# 8bitPig-PigstyGates_v2-frontPCB.net
KiCad netlist of a schematic drawn in EAGLE
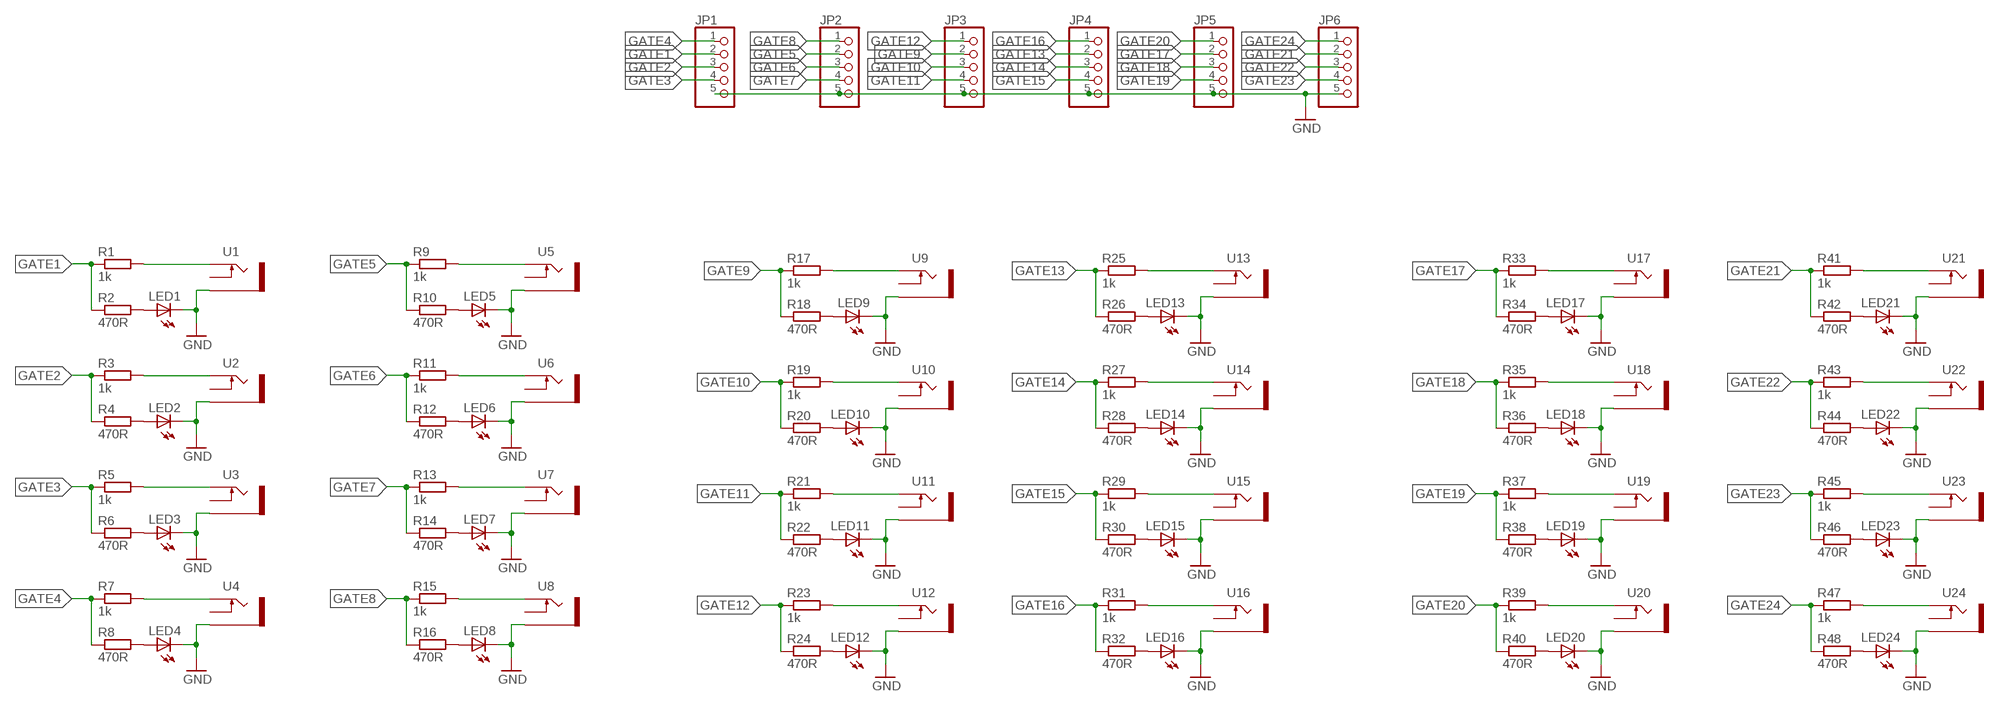
[diagram p0: schematic, sheet 1]

(export (version "E")
  (design (tool "Eeschema 10.0.6"))
  (components
    (comp (ref "JP1")
      (value "PINHD-1X5")
      (footprint "eagle-import:1X05")
      (libsource (lib "eagle-import") (part "PINHD-1X5"))
    )
    (comp (ref "JP2")
      (value "PINHD-1X5")
      (footprint "eagle-import:1X05")
      (libsource (lib "eagle-import") (part "PINHD-1X5"))
    )
    (comp (ref "JP3")
      (value "PINHD-1X5")
      (footprint "eagle-import:1X05")
      (libsource (lib "eagle-import") (part "PINHD-1X5"))
    )
    (comp (ref "JP4")
      (value "PINHD-1X5")
      (footprint "eagle-import:1X05")
      (libsource (lib "eagle-import") (part "PINHD-1X5"))
    )
    (comp (ref "JP5")
      (value "PINHD-1X5")
      (footprint "eagle-import:1X05")
      (libsource (lib "eagle-import") (part "PINHD-1X5"))
    )
    (comp (ref "JP6")
      (value "PINHD-1X5")
      (footprint "eagle-import:1X05")
      (libsource (lib "eagle-import") (part "PINHD-1X5"))
    )
    (comp (ref "LED1")
      (value "LED3MM")
      (footprint "eagle-import:LED3MM")
      (libsource (lib "eagle-import") (part "LED3MM"))
    )
    (comp (ref "LED2")
      (value "LED3MM")
      (footprint "eagle-import:LED3MM")
      (libsource (lib "eagle-import") (part "LED3MM"))
    )
    (comp (ref "LED3")
      (value "LED3MM")
      (footprint "eagle-import:LED3MM")
      (libsource (lib "eagle-import") (part "LED3MM"))
    )
    (comp (ref "LED4")
      (value "LED3MM")
      (footprint "eagle-import:LED3MM")
      (libsource (lib "eagle-import") (part "LED3MM"))
    )
    (comp (ref "LED5")
      (value "LED3MM")
      (footprint "eagle-import:LED3MM")
      (libsource (lib "eagle-import") (part "LED3MM"))
    )
    (comp (ref "LED6")
      (value "LED3MM")
      (footprint "eagle-import:LED3MM")
      (libsource (lib "eagle-import") (part "LED3MM"))
    )
    (comp (ref "LED7")
      (value "LED3MM")
      (footprint "eagle-import:LED3MM")
      (libsource (lib "eagle-import") (part "LED3MM"))
    )
    (comp (ref "LED8")
      (value "LED3MM")
      (footprint "eagle-import:LED3MM")
      (libsource (lib "eagle-import") (part "LED3MM"))
    )
    (comp (ref "LED9")
      (value "LED3MM")
      (footprint "eagle-import:LED3MM")
      (libsource (lib "eagle-import") (part "LED3MM"))
    )
    (comp (ref "LED10")
      (value "LED3MM")
      (footprint "eagle-import:LED3MM")
      (libsource (lib "eagle-import") (part "LED3MM"))
    )
    (comp (ref "LED11")
      (value "LED3MM")
      (footprint "eagle-import:LED3MM")
      (libsource (lib "eagle-import") (part "LED3MM"))
    )
    (comp (ref "LED12")
      (value "LED3MM")
      (footprint "eagle-import:LED3MM")
      (libsource (lib "eagle-import") (part "LED3MM"))
    )
    (comp (ref "LED13")
      (value "LED3MM")
      (footprint "eagle-import:LED3MM")
      (libsource (lib "eagle-import") (part "LED3MM"))
    )
    (comp (ref "LED14")
      (value "LED3MM")
      (footprint "eagle-import:LED3MM")
      (libsource (lib "eagle-import") (part "LED3MM"))
    )
    (comp (ref "LED15")
      (value "LED3MM")
      (footprint "eagle-import:LED3MM")
      (libsource (lib "eagle-import") (part "LED3MM"))
    )
    (comp (ref "LED16")
      (value "LED3MM")
      (footprint "eagle-import:LED3MM")
      (libsource (lib "eagle-import") (part "LED3MM"))
    )
    (comp (ref "LED17")
      (value "LED3MM")
      (footprint "eagle-import:LED3MM")
      (libsource (lib "eagle-import") (part "LED3MM"))
    )
    (comp (ref "LED18")
      (value "LED3MM")
      (footprint "eagle-import:LED3MM")
      (libsource (lib "eagle-import") (part "LED3MM"))
    )
    (comp (ref "LED19")
      (value "LED3MM")
      (footprint "eagle-import:LED3MM")
      (libsource (lib "eagle-import") (part "LED3MM"))
    )
    (comp (ref "LED20")
      (value "LED3MM")
      (footprint "eagle-import:LED3MM")
      (libsource (lib "eagle-import") (part "LED3MM"))
    )
    (comp (ref "LED21")
      (value "LED3MM")
      (footprint "eagle-import:LED3MM")
      (libsource (lib "eagle-import") (part "LED3MM"))
    )
    (comp (ref "LED22")
      (value "LED3MM")
      (footprint "eagle-import:LED3MM")
      (libsource (lib "eagle-import") (part "LED3MM"))
    )
    (comp (ref "LED23")
      (value "LED3MM")
      (footprint "eagle-import:LED3MM")
      (libsource (lib "eagle-import") (part "LED3MM"))
    )
    (comp (ref "LED24")
      (value "LED3MM")
      (footprint "eagle-import:LED3MM")
      (libsource (lib "eagle-import") (part "LED3MM"))
    )
    (comp (ref "R1")
      (value "1k")
      (footprint "eagle-import:R0603")
      (libsource (lib "eagle-import") (part "R-EU_R0603"))
    )
    (comp (ref "R2")
      (value "470R")
      (footprint "eagle-import:R0603")
      (libsource (lib "eagle-import") (part "R-EU_R0603"))
    )
    (comp (ref "R3")
      (value "1k")
      (footprint "eagle-import:R0603")
      (libsource (lib "eagle-import") (part "R-EU_R0603"))
    )
    (comp (ref "R4")
      (value "470R")
      (footprint "eagle-import:R0603")
      (libsource (lib "eagle-import") (part "R-EU_R0603"))
    )
    (comp (ref "R5")
      (value "1k")
      (footprint "eagle-import:R0603")
      (libsource (lib "eagle-import") (part "R-EU_R0603"))
    )
    (comp (ref "R6")
      (value "470R")
      (footprint "eagle-import:R0603")
      (libsource (lib "eagle-import") (part "R-EU_R0603"))
    )
    (comp (ref "R7")
      (value "1k")
      (footprint "eagle-import:R0603")
      (libsource (lib "eagle-import") (part "R-EU_R0603"))
    )
    (comp (ref "R8")
      (value "470R")
      (footprint "eagle-import:R0603")
      (libsource (lib "eagle-import") (part "R-EU_R0603"))
    )
    (comp (ref "R9")
      (value "1k")
      (footprint "eagle-import:R0603")
      (libsource (lib "eagle-import") (part "R-EU_R0603"))
    )
    (comp (ref "R10")
      (value "470R")
      (footprint "eagle-import:R0603")
      (libsource (lib "eagle-import") (part "R-EU_R0603"))
    )
    (comp (ref "R11")
      (value "1k")
      (footprint "eagle-import:R0603")
      (libsource (lib "eagle-import") (part "R-EU_R0603"))
    )
    (comp (ref "R12")
      (value "470R")
      (footprint "eagle-import:R0603")
      (libsource (lib "eagle-import") (part "R-EU_R0603"))
    )
    (comp (ref "R13")
      (value "1k")
      (footprint "eagle-import:R0603")
      (libsource (lib "eagle-import") (part "R-EU_R0603"))
    )
    (comp (ref "R14")
      (value "470R")
      (footprint "eagle-import:R0603")
      (libsource (lib "eagle-import") (part "R-EU_R0603"))
    )
    (comp (ref "R15")
      (value "1k")
      (footprint "eagle-import:R0603")
      (libsource (lib "eagle-import") (part "R-EU_R0603"))
    )
    (comp (ref "R16")
      (value "470R")
      (footprint "eagle-import:R0603")
      (libsource (lib "eagle-import") (part "R-EU_R0603"))
    )
    (comp (ref "R17")
      (value "1k")
      (footprint "eagle-import:R0603")
      (libsource (lib "eagle-import") (part "R-EU_R0603"))
    )
    (comp (ref "R18")
      (value "470R")
      (footprint "eagle-import:R0603")
      (libsource (lib "eagle-import") (part "R-EU_R0603"))
    )
    (comp (ref "R19")
      (value "1k")
      (footprint "eagle-import:R0603")
      (libsource (lib "eagle-import") (part "R-EU_R0603"))
    )
    (comp (ref "R20")
      (value "470R")
      (footprint "eagle-import:R0603")
      (libsource (lib "eagle-import") (part "R-EU_R0603"))
    )
    (comp (ref "R21")
      (value "1k")
      (footprint "eagle-import:R0603")
      (libsource (lib "eagle-import") (part "R-EU_R0603"))
    )
    (comp (ref "R22")
      (value "470R")
      (footprint "eagle-import:R0603")
      (libsource (lib "eagle-import") (part "R-EU_R0603"))
    )
    (comp (ref "R23")
      (value "1k")
      (footprint "eagle-import:R0603")
      (libsource (lib "eagle-import") (part "R-EU_R0603"))
    )
    (comp (ref "R24")
      (value "470R")
      (footprint "eagle-import:R0603")
      (libsource (lib "eagle-import") (part "R-EU_R0603"))
    )
    (comp (ref "R25")
      (value "1k")
      (footprint "eagle-import:R0603")
      (libsource (lib "eagle-import") (part "R-EU_R0603"))
    )
    (comp (ref "R26")
      (value "470R")
      (footprint "eagle-import:R0603")
      (libsource (lib "eagle-import") (part "R-EU_R0603"))
    )
    (comp (ref "R27")
      (value "1k")
      (footprint "eagle-import:R0603")
      (libsource (lib "eagle-import") (part "R-EU_R0603"))
    )
    (comp (ref "R28")
      (value "470R")
      (footprint "eagle-import:R0603")
      (libsource (lib "eagle-import") (part "R-EU_R0603"))
    )
    (comp (ref "R29")
      (value "1k")
      (footprint "eagle-import:R0603")
      (libsource (lib "eagle-import") (part "R-EU_R0603"))
    )
    (comp (ref "R30")
      (value "470R")
      (footprint "eagle-import:R0603")
      (libsource (lib "eagle-import") (part "R-EU_R0603"))
    )
    (comp (ref "R31")
      (value "1k")
      (footprint "eagle-import:R0603")
      (libsource (lib "eagle-import") (part "R-EU_R0603"))
    )
    (comp (ref "R32")
      (value "470R")
      (footprint "eagle-import:R0603")
      (libsource (lib "eagle-import") (part "R-EU_R0603"))
    )
    (comp (ref "R33")
      (value "1k")
      (footprint "eagle-import:R0603")
      (libsource (lib "eagle-import") (part "R-EU_R0603"))
    )
    (comp (ref "R34")
      (value "470R")
      (footprint "eagle-import:R0603")
      (libsource (lib "eagle-import") (part "R-EU_R0603"))
    )
    (comp (ref "R35")
      (value "1k")
      (footprint "eagle-import:R0603")
      (libsource (lib "eagle-import") (part "R-EU_R0603"))
    )
    (comp (ref "R36")
      (value "470R")
      (footprint "eagle-import:R0603")
      (libsource (lib "eagle-import") (part "R-EU_R0603"))
    )
    (comp (ref "R37")
      (value "1k")
      (footprint "eagle-import:R0603")
      (libsource (lib "eagle-import") (part "R-EU_R0603"))
    )
    (comp (ref "R38")
      (value "470R")
      (footprint "eagle-import:R0603")
      (libsource (lib "eagle-import") (part "R-EU_R0603"))
    )
    (comp (ref "R39")
      (value "1k")
      (footprint "eagle-import:R0603")
      (libsource (lib "eagle-import") (part "R-EU_R0603"))
    )
    (comp (ref "R40")
      (value "470R")
      (footprint "eagle-import:R0603")
      (libsource (lib "eagle-import") (part "R-EU_R0603"))
    )
    (comp (ref "R41")
      (value "1k")
      (footprint "eagle-import:R0603")
      (libsource (lib "eagle-import") (part "R-EU_R0603"))
    )
    (comp (ref "R42")
      (value "470R")
      (footprint "eagle-import:R0603")
      (libsource (lib "eagle-import") (part "R-EU_R0603"))
    )
    (comp (ref "R43")
      (value "1k")
      (footprint "eagle-import:R0603")
      (libsource (lib "eagle-import") (part "R-EU_R0603"))
    )
    (comp (ref "R44")
      (value "470R")
      (footprint "eagle-import:R0603")
      (libsource (lib "eagle-import") (part "R-EU_R0603"))
    )
    (comp (ref "R45")
      (value "1k")
      (footprint "eagle-import:R0603")
      (libsource (lib "eagle-import") (part "R-EU_R0603"))
    )
    (comp (ref "R46")
      (value "470R")
      (footprint "eagle-import:R0603")
      (libsource (lib "eagle-import") (part "R-EU_R0603"))
    )
    (comp (ref "R47")
      (value "1k")
      (footprint "eagle-import:R0603")
      (libsource (lib "eagle-import") (part "R-EU_R0603"))
    )
    (comp (ref "R48")
      (value "470R")
      (footprint "eagle-import:R0603")
      (libsource (lib "eagle-import") (part "R-EU_R0603"))
    )
    (comp (ref "U1")
      (value "THONKICONNNEW")
      (footprint "eagle-import:WQP-PJ301M-12_JACK")
      (libsource (lib "eagle-import") (part "THONKICONNNEW"))
    )
    (comp (ref "U2")
      (value "THONKICONNNEW")
      (footprint "eagle-import:WQP-PJ301M-12_JACK")
      (libsource (lib "eagle-import") (part "THONKICONNNEW"))
    )
    (comp (ref "U3")
      (value "THONKICONNNEW")
      (footprint "eagle-import:WQP-PJ301M-12_JACK")
      (libsource (lib "eagle-import") (part "THONKICONNNEW"))
    )
    (comp (ref "U4")
      (value "THONKICONNNEW")
      (footprint "eagle-import:WQP-PJ301M-12_JACK")
      (libsource (lib "eagle-import") (part "THONKICONNNEW"))
    )
    (comp (ref "U5")
      (value "THONKICONNNEW")
      (footprint "eagle-import:WQP-PJ301M-12_JACK")
      (libsource (lib "eagle-import") (part "THONKICONNNEW"))
    )
    (comp (ref "U6")
      (value "THONKICONNNEW")
      (footprint "eagle-import:WQP-PJ301M-12_JACK")
      (libsource (lib "eagle-import") (part "THONKICONNNEW"))
    )
    (comp (ref "U7")
      (value "THONKICONNNEW")
      (footprint "eagle-import:WQP-PJ301M-12_JACK")
      (libsource (lib "eagle-import") (part "THONKICONNNEW"))
    )
    (comp (ref "U8")
      (value "THONKICONNNEW")
      (footprint "eagle-import:WQP-PJ301M-12_JACK")
      (libsource (lib "eagle-import") (part "THONKICONNNEW"))
    )
    (comp (ref "U9")
      (value "THONKICONNNEW")
      (footprint "eagle-import:WQP-PJ301M-12_JACK")
      (libsource (lib "eagle-import") (part "THONKICONNNEW"))
    )
    (comp (ref "U10")
      (value "THONKICONNNEW")
      (footprint "eagle-import:WQP-PJ301M-12_JACK")
      (libsource (lib "eagle-import") (part "THONKICONNNEW"))
    )
    (comp (ref "U11")
      (value "THONKICONNNEW")
      (footprint "eagle-import:WQP-PJ301M-12_JACK")
      (libsource (lib "eagle-import") (part "THONKICONNNEW"))
    )
    (comp (ref "U12")
      (value "THONKICONNNEW")
      (footprint "eagle-import:WQP-PJ301M-12_JACK")
      (libsource (lib "eagle-import") (part "THONKICONNNEW"))
    )
    (comp (ref "U13")
      (value "THONKICONNNEW")
      (footprint "eagle-import:WQP-PJ301M-12_JACK")
      (libsource (lib "eagle-import") (part "THONKICONNNEW"))
    )
    (comp (ref "U14")
      (value "THONKICONNNEW")
      (footprint "eagle-import:WQP-PJ301M-12_JACK")
      (libsource (lib "eagle-import") (part "THONKICONNNEW"))
    )
    (comp (ref "U15")
      (value "THONKICONNNEW")
      (footprint "eagle-import:WQP-PJ301M-12_JACK")
      (libsource (lib "eagle-import") (part "THONKICONNNEW"))
    )
    (comp (ref "U16")
      (value "THONKICONNNEW")
      (footprint "eagle-import:WQP-PJ301M-12_JACK")
      (libsource (lib "eagle-import") (part "THONKICONNNEW"))
    )
    (comp (ref "U17")
      (value "THONKICONNNEW")
      (footprint "eagle-import:WQP-PJ301M-12_JACK")
      (libsource (lib "eagle-import") (part "THONKICONNNEW"))
    )
    (comp (ref "U18")
      (value "THONKICONNNEW")
      (footprint "eagle-import:WQP-PJ301M-12_JACK")
      (libsource (lib "eagle-import") (part "THONKICONNNEW"))
    )
    (comp (ref "U19")
      (value "THONKICONNNEW")
      (footprint "eagle-import:WQP-PJ301M-12_JACK")
      (libsource (lib "eagle-import") (part "THONKICONNNEW"))
    )
    (comp (ref "U20")
      (value "THONKICONNNEW")
      (footprint "eagle-import:WQP-PJ301M-12_JACK")
      (libsource (lib "eagle-import") (part "THONKICONNNEW"))
    )
    (comp (ref "U21")
      (value "THONKICONNNEW")
      (footprint "eagle-import:WQP-PJ301M-12_JACK")
      (libsource (lib "eagle-import") (part "THONKICONNNEW"))
    )
    (comp (ref "U22")
      (value "THONKICONNNEW")
      (footprint "eagle-import:WQP-PJ301M-12_JACK")
      (libsource (lib "eagle-import") (part "THONKICONNNEW"))
    )
    (comp (ref "U23")
      (value "THONKICONNNEW")
      (footprint "eagle-import:WQP-PJ301M-12_JACK")
      (libsource (lib "eagle-import") (part "THONKICONNNEW"))
    )
    (comp (ref "U24")
      (value "THONKICONNNEW")
      (footprint "eagle-import:WQP-PJ301M-12_JACK")
      (libsource (lib "eagle-import") (part "THONKICONNNEW"))
    )
  )
  (nets
    (net (code "1") (name "GATE1") (class "Default")
      (node (ref "JP1") (pin "2") (pinfunction "2_2") (pintype "passive"))
      (node (ref "R1") (pin "1") (pinfunction "1_1") (pintype "passive"))
      (node (ref "R2") (pin "1") (pinfunction "1_1") (pintype "passive"))
    )
    (net (code "2") (name "GATE2") (class "Default")
      (node (ref "JP1") (pin "3") (pinfunction "3_3") (pintype "passive"))
      (node (ref "R3") (pin "1") (pinfunction "1_1") (pintype "passive"))
      (node (ref "R4") (pin "1") (pinfunction "1_1") (pintype "passive"))
    )
    (net (code "3") (name "GATE3") (class "Default")
      (node (ref "JP1") (pin "4") (pinfunction "4_4") (pintype "passive"))
      (node (ref "R5") (pin "1") (pinfunction "1_1") (pintype "passive"))
      (node (ref "R6") (pin "1") (pinfunction "1_1") (pintype "passive"))
    )
    (net (code "4") (name "GATE4") (class "Default")
      (node (ref "JP1") (pin "1") (pinfunction "1_1") (pintype "passive"))
      (node (ref "R7") (pin "1") (pinfunction "1_1") (pintype "passive"))
      (node (ref "R8") (pin "1") (pinfunction "1_1") (pintype "passive"))
    )
    (net (code "5") (name "GATE5") (class "Default")
      (node (ref "JP2") (pin "2") (pinfunction "2_2") (pintype "passive"))
      (node (ref "R10") (pin "1") (pinfunction "1_1") (pintype "passive"))
      (node (ref "R9") (pin "1") (pinfunction "1_1") (pintype "passive"))
    )
    (net (code "6") (name "GATE6") (class "Default")
      (node (ref "JP2") (pin "3") (pinfunction "3_3") (pintype "passive"))
      (node (ref "R11") (pin "1") (pinfunction "1_1") (pintype "passive"))
      (node (ref "R12") (pin "1") (pinfunction "1_1") (pintype "passive"))
    )
    (net (code "7") (name "GATE7") (class "Default")
      (node (ref "JP2") (pin "4") (pinfunction "4_4") (pintype "passive"))
      (node (ref "R13") (pin "1") (pinfunction "1_1") (pintype "passive"))
      (node (ref "R14") (pin "1") (pinfunction "1_1") (pintype "passive"))
    )
    (net (code "8") (name "GATE8") (class "Default")
      (node (ref "JP2") (pin "1") (pinfunction "1_1") (pintype "passive"))
      (node (ref "R15") (pin "1") (pinfunction "1_1") (pintype "passive"))
      (node (ref "R16") (pin "1") (pinfunction "1_1") (pintype "passive"))
    )
    (net (code "9") (name "GATE9") (class "Default")
      (node (ref "JP3") (pin "2") (pinfunction "2_2") (pintype "passive"))
      (node (ref "R17") (pin "1") (pinfunction "1_1") (pintype "passive"))
      (node (ref "R18") (pin "1") (pinfunction "1_1") (pintype "passive"))
    )
    (net (code "10") (name "GATE10") (class "Default")
      (node (ref "JP3") (pin "3") (pinfunction "3_3") (pintype "passive"))
      (node (ref "R19") (pin "1") (pinfunction "1_1") (pintype "passive"))
      (node (ref "R20") (pin "1") (pinfunction "1_1") (pintype "passive"))
    )
    (net (code "11") (name "GATE11") (class "Default")
      (node (ref "JP3") (pin "4") (pinfunction "4_4") (pintype "passive"))
      (node (ref "R21") (pin "1") (pinfunction "1_1") (pintype "passive"))
      (node (ref "R22") (pin "1") (pinfunction "1_1") (pintype "passive"))
    )
    (net (code "12") (name "GATE12") (class "Default")
      (node (ref "JP3") (pin "1") (pinfunction "1_1") (pintype "passive"))
      (node (ref "R23") (pin "1") (pinfunction "1_1") (pintype "passive"))
      (node (ref "R24") (pin "1") (pinfunction "1_1") (pintype "passive"))
    )
    (net (code "13") (name "GATE13") (class "Default")
      (node (ref "JP4") (pin "2") (pinfunction "2_2") (pintype "passive"))
      (node (ref "R25") (pin "1") (pinfunction "1_1") (pintype "passive"))
      (node (ref "R26") (pin "1") (pinfunction "1_1") (pintype "passive"))
    )
    (net (code "14") (name "GATE14") (class "Default")
      (node (ref "JP4") (pin "3") (pinfunction "3_3") (pintype "passive"))
      (node (ref "R27") (pin "1") (pinfunction "1_1") (pintype "passive"))
      (node (ref "R28") (pin "1") (pinfunction "1_1") (pintype "passive"))
    )
    (net (code "15") (name "GATE15") (class "Default")
      (node (ref "JP4") (pin "4") (pinfunction "4_4") (pintype "passive"))
      (node (ref "R29") (pin "1") (pinfunction "1_1") (pintype "passive"))
      (node (ref "R30") (pin "1") (pinfunction "1_1") (pintype "passive"))
    )
    (net (code "16") (name "GATE16") (class "Default")
      (node (ref "JP4") (pin "1") (pinfunction "1_1") (pintype "passive"))
      (node (ref "R31") (pin "1") (pinfunction "1_1") (pintype "passive"))
      (node (ref "R32") (pin "1") (pinfunction "1_1") (pintype "passive"))
    )
    (net (code "17") (name "GATE17") (class "Default")
      (node (ref "JP5") (pin "2") (pinfunction "2_2") (pintype "passive"))
      (node (ref "R33") (pin "1") (pinfunction "1_1") (pintype "passive"))
      (node (ref "R34") (pin "1") (pinfunction "1_1") (pintype "passive"))
    )
    (net (code "18") (name "GATE18") (class "Default")
      (node (ref "JP5") (pin "3") (pinfunction "3_3") (pintype "passive"))
      (node (ref "R35") (pin "1") (pinfunction "1_1") (pintype "passive"))
      (node (ref "R36") (pin "1") (pinfunction "1_1") (pintype "passive"))
    )
    (net (code "19") (name "GATE19") (class "Default")
      (node (ref "JP5") (pin "4") (pinfunction "4_4") (pintype "passive"))
      (node (ref "R37") (pin "1") (pinfunction "1_1") (pintype "passive"))
      (node (ref "R38") (pin "1") (pinfunction "1_1") (pintype "passive"))
    )
    (net (code "20") (name "GATE20") (class "Default")
      (node (ref "JP5") (pin "1") (pinfunction "1_1") (pintype "passive"))
      (node (ref "R39") (pin "1") (pinfunction "1_1") (pintype "passive"))
      (node (ref "R40") (pin "1") (pinfunction "1_1") (pintype "passive"))
    )
    (net (code "21") (name "GATE21") (class "Default")
      (node (ref "JP6") (pin "2") (pinfunction "2_2") (pintype "passive"))
      (node (ref "R41") (pin "1") (pinfunction "1_1") (pintype "passive"))
      (node (ref "R42") (pin "1") (pinfunction "1_1") (pintype "passive"))
    )
    (net (code "22") (name "GATE22") (class "Default")
      (node (ref "JP6") (pin "3") (pinfunction "3_3") (pintype "passive"))
      (node (ref "R43") (pin "1") (pinfunction "1_1") (pintype "passive"))
      (node (ref "R44") (pin "1") (pinfunction "1_1") (pintype "passive"))
    )
    (net (code "23") (name "GATE23") (class "Default")
      (node (ref "JP6") (pin "4") (pinfunction "4_4") (pintype "passive"))
      (node (ref "R45") (pin "1") (pinfunction "1_1") (pintype "passive"))
      (node (ref "R46") (pin "1") (pinfunction "1_1") (pintype "passive"))
    )
    (net (code "24") (name "GATE24") (class "Default")
      (node (ref "JP6") (pin "1") (pinfunction "1_1") (pintype "passive"))
      (node (ref "R47") (pin "1") (pinfunction "1_1") (pintype "passive"))
      (node (ref "R48") (pin "1") (pinfunction "1_1") (pintype "passive"))
    )
    (net (code "25") (name "GND") (class "Default")
      (node (ref "JP1") (pin "5") (pinfunction "5_5") (pintype "passive"))
      (node (ref "JP2") (pin "5") (pinfunction "5_5") (pintype "passive"))
      (node (ref "JP3") (pin "5") (pinfunction "5_5") (pintype "passive"))
      (node (ref "JP4") (pin "5") (pinfunction "5_5") (pintype "passive"))
      (node (ref "JP5") (pin "5") (pinfunction "5_5") (pintype "passive"))
      (node (ref "JP6") (pin "5") (pinfunction "5_5") (pintype "passive"))
      (node (ref "LED1") (pin "K") (pinfunction "C_K") (pintype "passive"))
      (node (ref "LED10") (pin "K") (pinfunction "C_K") (pintype "passive"))
      (node (ref "LED11") (pin "K") (pinfunction "C_K") (pintype "passive"))
      (node (ref "LED12") (pin "K") (pinfunction "C_K") (pintype "passive"))
      (node (ref "LED13") (pin "K") (pinfunction "C_K") (pintype "passive"))
      (node (ref "LED14") (pin "K") (pinfunction "C_K") (pintype "passive"))
      (node (ref "LED15") (pin "K") (pinfunction "C_K") (pintype "passive"))
      (node (ref "LED16") (pin "K") (pinfunction "C_K") (pintype "passive"))
      (node (ref "LED17") (pin "K") (pinfunction "C_K") (pintype "passive"))
      (node (ref "LED18") (pin "K") (pinfunction "C_K") (pintype "passive"))
      (node (ref "LED19") (pin "K") (pinfunction "C_K") (pintype "passive"))
      (node (ref "LED2") (pin "K") (pinfunction "C_K") (pintype "passive"))
      (node (ref "LED20") (pin "K") (pinfunction "C_K") (pintype "passive"))
      (node (ref "LED21") (pin "K") (pinfunction "C_K") (pintype "passive"))
      (node (ref "LED22") (pin "K") (pinfunction "C_K") (pintype "passive"))
      (node (ref "LED23") (pin "K") (pinfunction "C_K") (pintype "passive"))
      (node (ref "LED24") (pin "K") (pinfunction "C_K") (pintype "passive"))
      (node (ref "LED3") (pin "K") (pinfunction "C_K") (pintype "passive"))
      (node (ref "LED4") (pin "K") (pinfunction "C_K") (pintype "passive"))
      (node (ref "LED5") (pin "K") (pinfunction "C_K") (pintype "passive"))
      (node (ref "LED6") (pin "K") (pinfunction "C_K") (pintype "passive"))
      (node (ref "LED7") (pin "K") (pinfunction "C_K") (pintype "passive"))
      (node (ref "LED8") (pin "K") (pinfunction "C_K") (pintype "passive"))
      (node (ref "LED9") (pin "K") (pinfunction "C_K") (pintype "passive"))
      (node (ref "U1") (pin "P$3_SLEEVE") (pinfunction "SLEEVE_P$3_SLEEVE") (pintype "passive"))
      (node (ref "U10") (pin "P$3_SLEEVE") (pinfunction "SLEEVE_P$3_SLEEVE") (pintype "passive"))
      (node (ref "U11") (pin "P$3_SLEEVE") (pinfunction "SLEEVE_P$3_SLEEVE") (pintype "passive"))
      (node (ref "U12") (pin "P$3_SLEEVE") (pinfunction "SLEEVE_P$3_SLEEVE") (pintype "passive"))
      (node (ref "U13") (pin "P$3_SLEEVE") (pinfunction "SLEEVE_P$3_SLEEVE") (pintype "passive"))
      (node (ref "U14") (pin "P$3_SLEEVE") (pinfunction "SLEEVE_P$3_SLEEVE") (pintype "passive"))
      (node (ref "U15") (pin "P$3_SLEEVE") (pinfunction "SLEEVE_P$3_SLEEVE") (pintype "passive"))
      (node (ref "U16") (pin "P$3_SLEEVE") (pinfunction "SLEEVE_P$3_SLEEVE") (pintype "passive"))
      (node (ref "U17") (pin "P$3_SLEEVE") (pinfunction "SLEEVE_P$3_SLEEVE") (pintype "passive"))
      (node (ref "U18") (pin "P$3_SLEEVE") (pinfunction "SLEEVE_P$3_SLEEVE") (pintype "passive"))
      (node (ref "U19") (pin "P$3_SLEEVE") (pinfunction "SLEEVE_P$3_SLEEVE") (pintype "passive"))
      (node (ref "U2") (pin "P$3_SLEEVE") (pinfunction "SLEEVE_P$3_SLEEVE") (pintype "passive"))
      (node (ref "U20") (pin "P$3_SLEEVE") (pinfunction "SLEEVE_P$3_SLEEVE") (pintype "passive"))
      (node (ref "U21") (pin "P$3_SLEEVE") (pinfunction "SLEEVE_P$3_SLEEVE") (pintype "passive"))
      (node (ref "U22") (pin "P$3_SLEEVE") (pinfunction "SLEEVE_P$3_SLEEVE") (pintype "passive"))
      (node (ref "U23") (pin "P$3_SLEEVE") (pinfunction "SLEEVE_P$3_SLEEVE") (pintype "passive"))
      (node (ref "U24") (pin "P$3_SLEEVE") (pinfunction "SLEEVE_P$3_SLEEVE") (pintype "passive"))
      (node (ref "U3") (pin "P$3_SLEEVE") (pinfunction "SLEEVE_P$3_SLEEVE") (pintype "passive"))
      (node (ref "U4") (pin "P$3_SLEEVE") (pinfunction "SLEEVE_P$3_SLEEVE") (pintype "passive"))
      (node (ref "U5") (pin "P$3_SLEEVE") (pinfunction "SLEEVE_P$3_SLEEVE") (pintype "passive"))
      (node (ref "U6") (pin "P$3_SLEEVE") (pinfunction "SLEEVE_P$3_SLEEVE") (pintype "passive"))
      (node (ref "U7") (pin "P$3_SLEEVE") (pinfunction "SLEEVE_P$3_SLEEVE") (pintype "passive"))
      (node (ref "U8") (pin "P$3_SLEEVE") (pinfunction "SLEEVE_P$3_SLEEVE") (pintype "passive"))
      (node (ref "U9") (pin "P$3_SLEEVE") (pinfunction "SLEEVE_P$3_SLEEVE") (pintype "passive"))
    )
    (net (code "26") (name "Net-(LED1-PadA)") (class "Default")
      (node (ref "LED1") (pin "A") (pinfunction "A_A") (pintype "passive"))
      (node (ref "R2") (pin "2") (pinfunction "2_2") (pintype "passive"))
    )
    (net (code "27") (name "Net-(LED2-PadA)") (class "Default")
      (node (ref "LED2") (pin "A") (pinfunction "A_A") (pintype "passive"))
      (node (ref "R4") (pin "2") (pinfunction "2_2") (pintype "passive"))
    )
    (net (code "28") (name "Net-(LED3-PadA)") (class "Default")
      (node (ref "LED3") (pin "A") (pinfunction "A_A") (pintype "passive"))
      (node (ref "R6") (pin "2") (pinfunction "2_2") (pintype "passive"))
    )
    (net (code "29") (name "Net-(LED4-PadA)") (class "Default")
      (node (ref "LED4") (pin "A") (pinfunction "A_A") (pintype "passive"))
      (node (ref "R8") (pin "2") (pinfunction "2_2") (pintype "passive"))
    )
    (net (code "30") (name "Net-(LED5-PadA)") (class "Default")
      (node (ref "LED5") (pin "A") (pinfunction "A_A") (pintype "passive"))
      (node (ref "R10") (pin "2") (pinfunction "2_2") (pintype "passive"))
    )
    (net (code "31") (name "Net-(LED6-PadA)") (class "Default")
      (node (ref "LED6") (pin "A") (pinfunction "A_A") (pintype "passive"))
      (node (ref "R12") (pin "2") (pinfunction "2_2") (pintype "passive"))
    )
    (net (code "32") (name "Net-(LED7-PadA)") (class "Default")
      (node (ref "LED7") (pin "A") (pinfunction "A_A") (pintype "passive"))
      (node (ref "R14") (pin "2") (pinfunction "2_2") (pintype "passive"))
    )
    (net (code "33") (name "Net-(LED8-PadA)") (class "Default")
      (node (ref "LED8") (pin "A") (pinfunction "A_A") (pintype "passive"))
      (node (ref "R16") (pin "2") (pinfunction "2_2") (pintype "passive"))
    )
    (net (code "34") (name "Net-(LED9-PadA)") (class "Default")
      (node (ref "LED9") (pin "A") (pinfunction "A_A") (pintype "passive"))
      (node (ref "R18") (pin "2") (pinfunction "2_2") (pintype "passive"))
    )
    (net (code "35") (name "Net-(LED10-PadA)") (class "Default")
      (node (ref "LED10") (pin "A") (pinfunction "A_A") (pintype "passive"))
      (node (ref "R20") (pin "2") (pinfunction "2_2") (pintype "passive"))
    )
    (net (code "36") (name "Net-(LED11-PadA)") (class "Default")
      (node (ref "LED11") (pin "A") (pinfunction "A_A") (pintype "passive"))
      (node (ref "R22") (pin "2") (pinfunction "2_2") (pintype "passive"))
    )
    (net (code "37") (name "Net-(LED12-PadA)") (class "Default")
      (node (ref "LED12") (pin "A") (pinfunction "A_A") (pintype "passive"))
      (node (ref "R24") (pin "2") (pinfunction "2_2") (pintype "passive"))
    )
    (net (code "38") (name "Net-(LED13-PadA)") (class "Default")
      (node (ref "LED13") (pin "A") (pinfunction "A_A") (pintype "passive"))
      (node (ref "R26") (pin "2") (pinfunction "2_2") (pintype "passive"))
    )
    (net (code "39") (name "Net-(LED14-PadA)") (class "Default")
      (node (ref "LED14") (pin "A") (pinfunction "A_A") (pintype "passive"))
      (node (ref "R28") (pin "2") (pinfunction "2_2") (pintype "passive"))
    )
    (net (code "40") (name "Net-(LED15-PadA)") (class "Default")
      (node (ref "LED15") (pin "A") (pinfunction "A_A") (pintype "passive"))
      (node (ref "R30") (pin "2") (pinfunction "2_2") (pintype "passive"))
    )
    (net (code "41") (name "Net-(LED16-PadA)") (class "Default")
      (node (ref "LED16") (pin "A") (pinfunction "A_A") (pintype "passive"))
      (node (ref "R32") (pin "2") (pinfunction "2_2") (pintype "passive"))
    )
    (net (code "42") (name "Net-(LED17-PadA)") (class "Default")
      (node (ref "LED17") (pin "A") (pinfunction "A_A") (pintype "passive"))
      (node (ref "R34") (pin "2") (pinfunction "2_2") (pintype "passive"))
    )
    (net (code "43") (name "Net-(LED18-PadA)") (class "Default")
      (node (ref "LED18") (pin "A") (pinfunction "A_A") (pintype "passive"))
      (node (ref "R36") (pin "2") (pinfunction "2_2") (pintype "passive"))
    )
    (net (code "44") (name "Net-(LED19-PadA)") (class "Default")
      (node (ref "LED19") (pin "A") (pinfunction "A_A") (pintype "passive"))
      (node (ref "R38") (pin "2") (pinfunction "2_2") (pintype "passive"))
    )
    (net (code "45") (name "Net-(LED20-PadA)") (class "Default")
      (node (ref "LED20") (pin "A") (pinfunction "A_A") (pintype "passive"))
      (node (ref "R40") (pin "2") (pinfunction "2_2") (pintype "passive"))
    )
    (net (code "46") (name "Net-(LED21-PadA)") (class "Default")
      (node (ref "LED21") (pin "A") (pinfunction "A_A") (pintype "passive"))
      (node (ref "R42") (pin "2") (pinfunction "2_2") (pintype "passive"))
    )
    (net (code "47") (name "Net-(LED22-PadA)") (class "Default")
      (node (ref "LED22") (pin "A") (pinfunction "A_A") (pintype "passive"))
      (node (ref "R44") (pin "2") (pinfunction "2_2") (pintype "passive"))
    )
    (net (code "48") (name "Net-(LED23-PadA)") (class "Default")
      (node (ref "LED23") (pin "A") (pinfunction "A_A") (pintype "passive"))
      (node (ref "R46") (pin "2") (pinfunction "2_2") (pintype "passive"))
    )
    (net (code "49") (name "Net-(LED24-PadA)") (class "Default")
      (node (ref "LED24") (pin "A") (pinfunction "A_A") (pintype "passive"))
      (node (ref "R48") (pin "2") (pinfunction "2_2") (pintype "passive"))
    )
    (net (code "50") (name "Net-(U1-TIP)") (class "Default")
      (node (ref "R1") (pin "2") (pinfunction "2_2") (pintype "passive"))
      (node (ref "U1") (pin "P$1_TIP") (pinfunction "TIP_P$1_TIP") (pintype "passive"))
    )
    (net (code "51") (name "Net-(U2-TIP)") (class "Default")
      (node (ref "R3") (pin "2") (pinfunction "2_2") (pintype "passive"))
      (node (ref "U2") (pin "P$1_TIP") (pinfunction "TIP_P$1_TIP") (pintype "passive"))
    )
    (net (code "52") (name "Net-(U3-TIP)") (class "Default")
      (node (ref "R5") (pin "2") (pinfunction "2_2") (pintype "passive"))
      (node (ref "U3") (pin "P$1_TIP") (pinfunction "TIP_P$1_TIP") (pintype "passive"))
    )
    (net (code "53") (name "Net-(U4-TIP)") (class "Default")
      (node (ref "R7") (pin "2") (pinfunction "2_2") (pintype "passive"))
      (node (ref "U4") (pin "P$1_TIP") (pinfunction "TIP_P$1_TIP") (pintype "passive"))
    )
    (net (code "54") (name "Net-(U5-TIP)") (class "Default")
      (node (ref "R9") (pin "2") (pinfunction "2_2") (pintype "passive"))
      (node (ref "U5") (pin "P$1_TIP") (pinfunction "TIP_P$1_TIP") (pintype "passive"))
    )
    (net (code "55") (name "Net-(U6-TIP)") (class "Default")
      (node (ref "R11") (pin "2") (pinfunction "2_2") (pintype "passive"))
      (node (ref "U6") (pin "P$1_TIP") (pinfunction "TIP_P$1_TIP") (pintype "passive"))
    )
    (net (code "56") (name "Net-(U7-TIP)") (class "Default")
      (node (ref "R13") (pin "2") (pinfunction "2_2") (pintype "passive"))
      (node (ref "U7") (pin "P$1_TIP") (pinfunction "TIP_P$1_TIP") (pintype "passive"))
    )
    (net (code "57") (name "Net-(U8-TIP)") (class "Default")
      (node (ref "R15") (pin "2") (pinfunction "2_2") (pintype "passive"))
      (node (ref "U8") (pin "P$1_TIP") (pinfunction "TIP_P$1_TIP") (pintype "passive"))
    )
    (net (code "58") (name "Net-(U9-TIP)") (class "Default")
      (node (ref "R17") (pin "2") (pinfunction "2_2") (pintype "passive"))
      (node (ref "U9") (pin "P$1_TIP") (pinfunction "TIP_P$1_TIP") (pintype "passive"))
    )
    (net (code "59") (name "Net-(U10-TIP)") (class "Default")
      (node (ref "R19") (pin "2") (pinfunction "2_2") (pintype "passive"))
      (node (ref "U10") (pin "P$1_TIP") (pinfunction "TIP_P$1_TIP") (pintype "passive"))
    )
    (net (code "60") (name "Net-(U11-TIP)") (class "Default")
      (node (ref "R21") (pin "2") (pinfunction "2_2") (pintype "passive"))
      (node (ref "U11") (pin "P$1_TIP") (pinfunction "TIP_P$1_TIP") (pintype "passive"))
    )
    (net (code "61") (name "Net-(U12-TIP)") (class "Default")
      (node (ref "R23") (pin "2") (pinfunction "2_2") (pintype "passive"))
      (node (ref "U12") (pin "P$1_TIP") (pinfunction "TIP_P$1_TIP") (pintype "passive"))
    )
    (net (code "62") (name "Net-(U13-TIP)") (class "Default")
      (node (ref "R25") (pin "2") (pinfunction "2_2") (pintype "passive"))
      (node (ref "U13") (pin "P$1_TIP") (pinfunction "TIP_P$1_TIP") (pintype "passive"))
    )
    (net (code "63") (name "Net-(U14-TIP)") (class "Default")
      (node (ref "R27") (pin "2") (pinfunction "2_2") (pintype "passive"))
      (node (ref "U14") (pin "P$1_TIP") (pinfunction "TIP_P$1_TIP") (pintype "passive"))
    )
    (net (code "64") (name "Net-(U15-TIP)") (class "Default")
      (node (ref "R29") (pin "2") (pinfunction "2_2") (pintype "passive"))
      (node (ref "U15") (pin "P$1_TIP") (pinfunction "TIP_P$1_TIP") (pintype "passive"))
    )
    (net (code "65") (name "Net-(U16-TIP)") (class "Default")
      (node (ref "R31") (pin "2") (pinfunction "2_2") (pintype "passive"))
      (node (ref "U16") (pin "P$1_TIP") (pinfunction "TIP_P$1_TIP") (pintype "passive"))
    )
    (net (code "66") (name "Net-(U17-TIP)") (class "Default")
      (node (ref "R33") (pin "2") (pinfunction "2_2") (pintype "passive"))
      (node (ref "U17") (pin "P$1_TIP") (pinfunction "TIP_P$1_TIP") (pintype "passive"))
    )
    (net (code "67") (name "Net-(U18-TIP)") (class "Default")
      (node (ref "R35") (pin "2") (pinfunction "2_2") (pintype "passive"))
      (node (ref "U18") (pin "P$1_TIP") (pinfunction "TIP_P$1_TIP") (pintype "passive"))
    )
    (net (code "68") (name "Net-(U19-TIP)") (class "Default")
      (node (ref "R37") (pin "2") (pinfunction "2_2") (pintype "passive"))
      (node (ref "U19") (pin "P$1_TIP") (pinfunction "TIP_P$1_TIP") (pintype "passive"))
    )
    (net (code "69") (name "Net-(U20-TIP)") (class "Default")
      (node (ref "R39") (pin "2") (pinfunction "2_2") (pintype "passive"))
      (node (ref "U20") (pin "P$1_TIP") (pinfunction "TIP_P$1_TIP") (pintype "passive"))
    )
    (net (code "70") (name "Net-(U21-TIP)") (class "Default")
      (node (ref "R41") (pin "2") (pinfunction "2_2") (pintype "passive"))
      (node (ref "U21") (pin "P$1_TIP") (pinfunction "TIP_P$1_TIP") (pintype "passive"))
    )
    (net (code "71") (name "Net-(U22-TIP)") (class "Default")
      (node (ref "R43") (pin "2") (pinfunction "2_2") (pintype "passive"))
      (node (ref "U22") (pin "P$1_TIP") (pinfunction "TIP_P$1_TIP") (pintype "passive"))
    )
    (net (code "72") (name "Net-(U23-TIP)") (class "Default")
      (node (ref "R45") (pin "2") (pinfunction "2_2") (pintype "passive"))
      (node (ref "U23") (pin "P$1_TIP") (pinfunction "TIP_P$1_TIP") (pintype "passive"))
    )
    (net (code "73") (name "Net-(U24-TIP)") (class "Default")
      (node (ref "R47") (pin "2") (pinfunction "2_2") (pintype "passive"))
      (node (ref "U24") (pin "P$1_TIP") (pinfunction "TIP_P$1_TIP") (pintype "passive"))
    )
    (net (code "74") (name "unconnected-(U1-SWITCH-PadP$2_SWITCH)") (class "Default")
      (node (ref "U1") (pin "P$2_SWITCH") (pinfunction "SWITCH_P$2_SWITCH") (pintype "passive"))
    )
    (net (code "75") (name "unconnected-(U2-SWITCH-PadP$2_SWITCH)") (class "Default")
      (node (ref "U2") (pin "P$2_SWITCH") (pinfunction "SWITCH_P$2_SWITCH") (pintype "passive"))
    )
    (net (code "76") (name "unconnected-(U3-SWITCH-PadP$2_SWITCH)") (class "Default")
      (node (ref "U3") (pin "P$2_SWITCH") (pinfunction "SWITCH_P$2_SWITCH") (pintype "passive"))
    )
    (net (code "77") (name "unconnected-(U4-SWITCH-PadP$2_SWITCH)") (class "Default")
      (node (ref "U4") (pin "P$2_SWITCH") (pinfunction "SWITCH_P$2_SWITCH") (pintype "passive"))
    )
    (net (code "78") (name "unconnected-(U5-SWITCH-PadP$2_SWITCH)") (class "Default")
      (node (ref "U5") (pin "P$2_SWITCH") (pinfunction "SWITCH_P$2_SWITCH") (pintype "passive"))
    )
    (net (code "79") (name "unconnected-(U6-SWITCH-PadP$2_SWITCH)") (class "Default")
      (node (ref "U6") (pin "P$2_SWITCH") (pinfunction "SWITCH_P$2_SWITCH") (pintype "passive"))
    )
    (net (code "80") (name "unconnected-(U7-SWITCH-PadP$2_SWITCH)") (class "Default")
      (node (ref "U7") (pin "P$2_SWITCH") (pinfunction "SWITCH_P$2_SWITCH") (pintype "passive"))
    )
    (net (code "81") (name "unconnected-(U8-SWITCH-PadP$2_SWITCH)") (class "Default")
      (node (ref "U8") (pin "P$2_SWITCH") (pinfunction "SWITCH_P$2_SWITCH") (pintype "passive"))
    )
    (net (code "82") (name "unconnected-(U9-SWITCH-PadP$2_SWITCH)") (class "Default")
      (node (ref "U9") (pin "P$2_SWITCH") (pinfunction "SWITCH_P$2_SWITCH") (pintype "passive"))
    )
    (net (code "83") (name "unconnected-(U10-SWITCH-PadP$2_SWITCH)") (class "Default")
      (node (ref "U10") (pin "P$2_SWITCH") (pinfunction "SWITCH_P$2_SWITCH") (pintype "passive"))
    )
    (net (code "84") (name "unconnected-(U11-SWITCH-PadP$2_SWITCH)") (class "Default")
      (node (ref "U11") (pin "P$2_SWITCH") (pinfunction "SWITCH_P$2_SWITCH") (pintype "passive"))
    )
    (net (code "85") (name "unconnected-(U12-SWITCH-PadP$2_SWITCH)") (class "Default")
      (node (ref "U12") (pin "P$2_SWITCH") (pinfunction "SWITCH_P$2_SWITCH") (pintype "passive"))
    )
    (net (code "86") (name "unconnected-(U13-SWITCH-PadP$2_SWITCH)") (class "Default")
      (node (ref "U13") (pin "P$2_SWITCH") (pinfunction "SWITCH_P$2_SWITCH") (pintype "passive"))
    )
    (net (code "87") (name "unconnected-(U14-SWITCH-PadP$2_SWITCH)") (class "Default")
      (node (ref "U14") (pin "P$2_SWITCH") (pinfunction "SWITCH_P$2_SWITCH") (pintype "passive"))
    )
    (net (code "88") (name "unconnected-(U15-SWITCH-PadP$2_SWITCH)") (class "Default")
      (node (ref "U15") (pin "P$2_SWITCH") (pinfunction "SWITCH_P$2_SWITCH") (pintype "passive"))
    )
    (net (code "89") (name "unconnected-(U16-SWITCH-PadP$2_SWITCH)") (class "Default")
      (node (ref "U16") (pin "P$2_SWITCH") (pinfunction "SWITCH_P$2_SWITCH") (pintype "passive"))
    )
    (net (code "90") (name "unconnected-(U17-SWITCH-PadP$2_SWITCH)") (class "Default")
      (node (ref "U17") (pin "P$2_SWITCH") (pinfunction "SWITCH_P$2_SWITCH") (pintype "passive"))
    )
    (net (code "91") (name "unconnected-(U18-SWITCH-PadP$2_SWITCH)") (class "Default")
      (node (ref "U18") (pin "P$2_SWITCH") (pinfunction "SWITCH_P$2_SWITCH") (pintype "passive"))
    )
    (net (code "92") (name "unconnected-(U19-SWITCH-PadP$2_SWITCH)") (class "Default")
      (node (ref "U19") (pin "P$2_SWITCH") (pinfunction "SWITCH_P$2_SWITCH") (pintype "passive"))
    )
    (net (code "93") (name "unconnected-(U20-SWITCH-PadP$2_SWITCH)") (class "Default")
      (node (ref "U20") (pin "P$2_SWITCH") (pinfunction "SWITCH_P$2_SWITCH") (pintype "passive"))
    )
    (net (code "94") (name "unconnected-(U21-SWITCH-PadP$2_SWITCH)") (class "Default")
      (node (ref "U21") (pin "P$2_SWITCH") (pinfunction "SWITCH_P$2_SWITCH") (pintype "passive"))
    )
    (net (code "95") (name "unconnected-(U22-SWITCH-PadP$2_SWITCH)") (class "Default")
      (node (ref "U22") (pin "P$2_SWITCH") (pinfunction "SWITCH_P$2_SWITCH") (pintype "passive"))
    )
    (net (code "96") (name "unconnected-(U23-SWITCH-PadP$2_SWITCH)") (class "Default")
      (node (ref "U23") (pin "P$2_SWITCH") (pinfunction "SWITCH_P$2_SWITCH") (pintype "passive"))
    )
    (net (code "97") (name "unconnected-(U24-SWITCH-PadP$2_SWITCH)") (class "Default")
      (node (ref "U24") (pin "P$2_SWITCH") (pinfunction "SWITCH_P$2_SWITCH") (pintype "passive"))
    )
  )
)
